# PolluxSensorDust.net
KiCad netlist of a schematic drawn in EAGLE
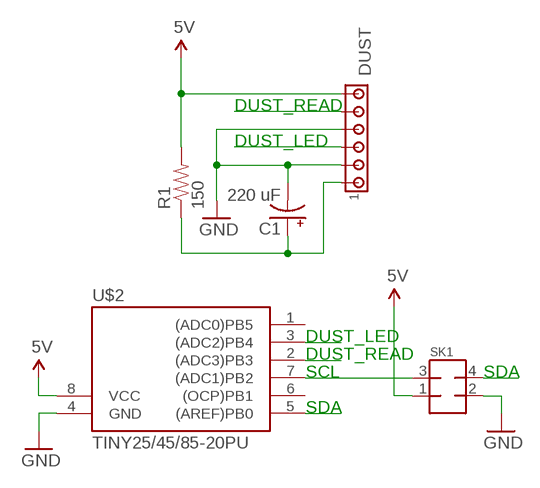
[diagram p0: schematic, sheet 1]

(export (version "E")
  (design (tool "Eeschema 10.0.6"))
  (components
    (comp (ref "C1")
      (value "220 uF")
      (footprint "eagle-import:CPOL-RADIAL-1000UF-25V")
      (libsource (lib "eagle-import") (part "CAP_POLPTH4"))
    )
    (comp (ref "DUST")
      (value "MTA06-100")
      (footprint "eagle-import:10X06MTA")
      (libsource (lib "eagle-import") (part "MTA06-100"))
    )
    (comp (ref "R1")
      (value "150")
      (footprint "eagle-import:AXIAL-0.3")
      (libsource (lib "eagle-import") (part "RESISTORAXIAL-0.3"))
    )
    (comp (ref "SK1")
      (value "MMATCH-8-PTH")
      (footprint "eagle-import:AMP-215079-8")
      (libsource (lib "eagle-import") (part "MMATCH-8-PTH"))
    )
    (comp (ref "U$2")
      (value "TINY25/45/85-20PU")
      (footprint "eagle-import:DIL08")
      (libsource (lib "eagle-import") (part "TINY25/45/85-20PU"))
    )
  )
  (nets
    (net (code "1") (name "/DUST_LED") (class "Default")
      (node (ref "DUST") (pin "4") (pinfunction "3_4") (pintype "passive"))
      (node (ref "U$2") (pin "3") (pinfunction "(ADC2)PB4_3") (pintype "bidirectional"))
    )
    (net (code "2") (name "/DUST_READ") (class "Default")
      (node (ref "DUST") (pin "2") (pinfunction "5_2") (pintype "passive"))
      (node (ref "U$2") (pin "2") (pinfunction "(ADC3)PB3_2") (pintype "bidirectional"))
    )
    (net (code "3") (name "/SDA") (class "Default")
      (node (ref "SK1") (pin "4") (pinfunction "4_4") (pintype "bidirectional"))
      (node (ref "U$2") (pin "5") (pinfunction "(AREF)PB0_5") (pintype "bidirectional"))
    )
    (net (code "4") (name "5V") (class "Default")
      (node (ref "DUST") (pin "1") (pinfunction "6_1") (pintype "passive"))
      (node (ref "R1") (pin "P$2") (pinfunction "2_P$2") (pintype "passive"))
      (node (ref "SK1") (pin "1") (pinfunction "1_1") (pintype "bidirectional"))
      (node (ref "U$2") (pin "8") (pinfunction "VCC_8") (pintype "power_in"))
    )
    (net (code "5") (name "GND") (class "Default")
      (node (ref "C1") (pin "2") (pinfunction "-_2") (pintype "passive"))
      (node (ref "DUST") (pin "3") (pinfunction "4_3") (pintype "passive"))
      (node (ref "DUST") (pin "5") (pinfunction "2_5") (pintype "passive"))
      (node (ref "SK1") (pin "2") (pinfunction "2_2") (pintype "bidirectional"))
      (node (ref "U$2") (pin "4") (pinfunction "GND_4") (pintype "power_in"))
    )
    (net (code "6") (name "Net-(C1-+)") (class "Default")
      (node (ref "C1") (pin "1") (pinfunction "+_1") (pintype "passive"))
      (node (ref "DUST") (pin "6") (pinfunction "1_6") (pintype "passive"))
      (node (ref "R1") (pin "P$1") (pinfunction "1_P$1") (pintype "passive"))
    )
    (net (code "7") (name "Net-(U$2-(ADC1)PB2)") (class "Default")
      (node (ref "SK1") (pin "3") (pinfunction "3_3") (pintype "bidirectional"))
      (node (ref "U$2") (pin "7") (pinfunction "(ADC1)PB2_7") (pintype "bidirectional"))
    )
    (net (code "8") (name "unconnected-(U$2-(ADC0)PB5-Pad1)") (class "Default")
      (node (ref "U$2") (pin "1") (pinfunction "(ADC0)PB5_1") (pintype "bidirectional"))
    )
    (net (code "9") (name "unconnected-(U$2-(OCP)PB1-Pad6)") (class "Default")
      (node (ref "U$2") (pin "6") (pinfunction "(OCP)PB1_6") (pintype "bidirectional"))
    )
  )
)
